# RasPi-BplusHAT_CamSlot.net
KiCad netlist of a schematic drawn in EAGLE
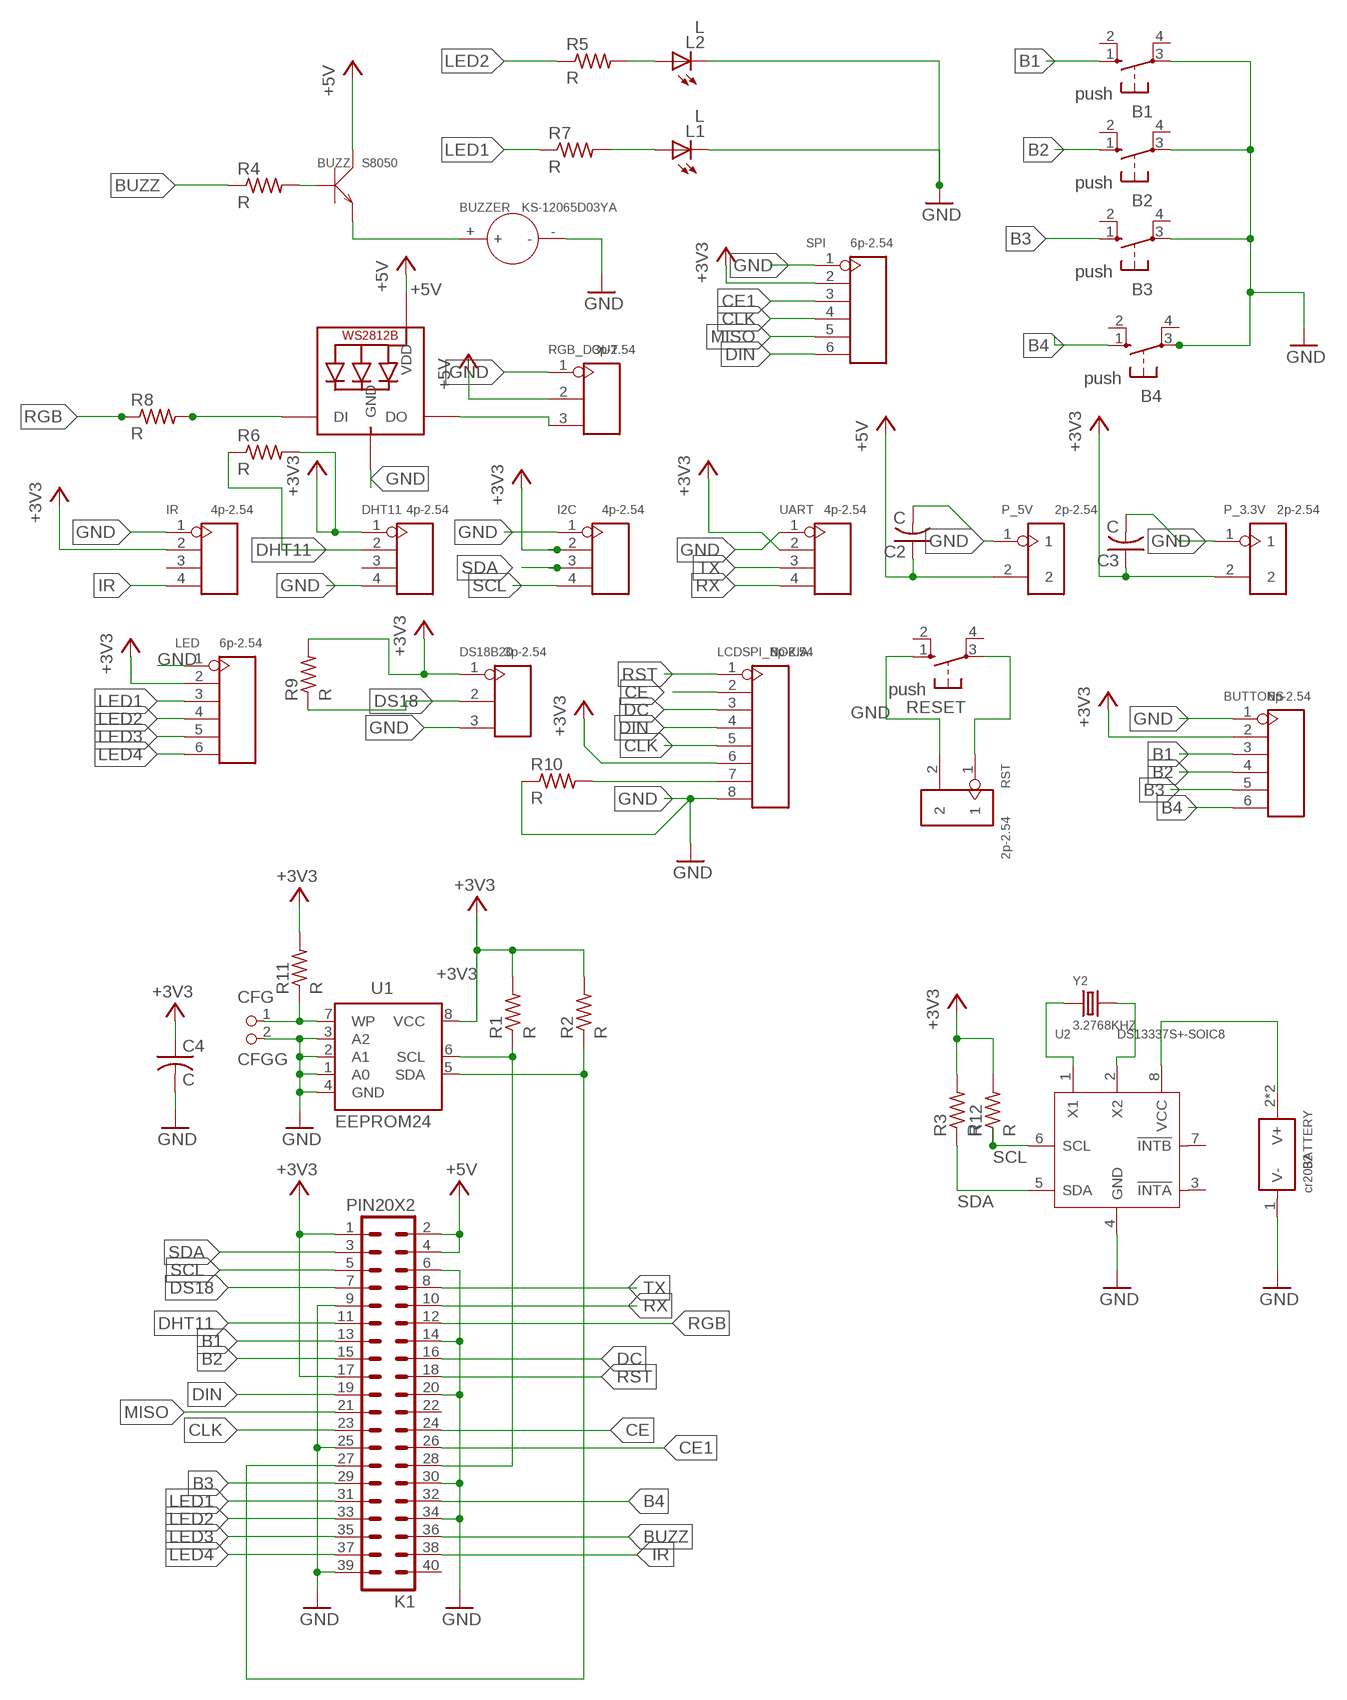
[diagram p0: schematic, sheet 1]

(export (version "E")
  (design (tool "Eeschema 10.0.6"))
  (components
    (comp (ref "B1")
      (value "push")
      (footprint "eagle-import:B3F-10XX")
      (fields (field (name "MPN") "B3F-1000"))
      (libsource (lib "eagle-import") (part "10-XX"))
    )
    (comp (ref "B2")
      (value "push")
      (footprint "eagle-import:B3F-10XX")
      (fields (field (name "MPN") "B3F-1000"))
      (libsource (lib "eagle-import") (part "10-XX"))
    )
    (comp (ref "B3")
      (value "push")
      (footprint "eagle-import:B3F-10XX")
      (fields (field (name "MPN") "B3F-1000"))
      (libsource (lib "eagle-import") (part "10-XX"))
    )
    (comp (ref "B4")
      (value "push")
      (footprint "eagle-import:B3F-10XX")
      (fields (field (name "MPN") "B3F-1000"))
      (libsource (lib "eagle-import") (part "10-XX"))
    )
    (comp (ref "BATTERY")
      (value "cr2032")
      (footprint "eagle-import:BAT2P-20.32-CR2032")
      (libsource (lib "eagle-import") (part "DIP-BATTERY-CELL-HOLDER(2032)"))
    )
    (comp (ref "BUTTONS")
      (value "6p-2.54")
      (footprint "eagle-import:H6-2.54")
      (fields (field (name "MPN") "F185-1106A1BSYC1"))
      (libsource (lib "eagle-import") (part "DIP-BLACK-FEMALE-HEADER-VERT(6P-2.54)"))
    )
    (comp (ref "BUZZ")
      (value "S8050")
      (footprint "eagle-import:SOT-23")
      (libsource (lib "eagle-import") (part "SMD-TRANSISTORS-NPN-25V-500MW-S8050(SOT-23)"))
    )
    (comp (ref "BUZZER")
      (value "KS-12065D03YA")
      (footprint "eagle-import:BZ2-7.6-D12.0XH6.5MM")
      (libsource (lib "eagle-import") (part "DIP-BUZZER-3V(KS-12065D03YA)"))
    )
    (comp (ref "C2")
      (value "C")
      (footprint "eagle-import:C1206")
      (libsource (lib "eagle-import") (part "C-USC1206"))
    )
    (comp (ref "C3")
      (value "C")
      (footprint "eagle-import:C1206")
      (libsource (lib "eagle-import") (part "C-USC1206"))
    )
    (comp (ref "C4")
      (value "C")
      (footprint "eagle-import:C1206")
      (libsource (lib "eagle-import") (part "C-USC1206"))
    )
    (comp (ref "CFG")
      (value "CFGG")
      (footprint "eagle-import:PIN_W_2")
      (libsource (lib "eagle-import") (part "PIN2_100"))
    )
    (comp (ref "DHT11")
      (value "4p-2.54")
      (footprint "eagle-import:H4-2.54")
      (fields (field (name "MPN") "F185-1104A1BSYA1"))
      (libsource (lib "eagle-import") (part "DIP-BLACK-FEMALE-HEADER-VERT(4P-2.54)"))
    )
    (comp (ref "DS18B20")
      (value "3p-2.54")
      (footprint "eagle-import:H3-2.54")
      (libsource (lib "eagle-import") (part "DIP-BLACK-MALE-HEADER-VERT(3P-2.54)"))
    )
    (comp (ref "I2C")
      (value "4p-2.54")
      (footprint "eagle-import:H4-2.54")
      (fields (field (name "MPN") "F185-1104A1BSYA1"))
      (libsource (lib "eagle-import") (part "DIP-BLACK-FEMALE-HEADER-VERT(4P-2.54)"))
    )
    (comp (ref "IR")
      (value "4p-2.54")
      (footprint "eagle-import:H4-2.54")
      (fields (field (name "MPN") "F185-1104A1BSYA1"))
      (libsource (lib "eagle-import") (part "DIP-BLACK-FEMALE-HEADER-VERT(4P-2.54)"))
    )
    (comp (ref "K1")
      (value "PIN20X2")
      (footprint "eagle-import:PIN_20X2")
      (libsource (lib "eagle-import") (part "PIN20X2"))
    )
    (comp (ref "L1")
      (value "L")
      (footprint "eagle-import:LED5MM")
      (libsource (lib "eagle-import") (part "LED5MM"))
    )
    (comp (ref "L2")
      (value "L")
      (footprint "eagle-import:LED5MM")
      (libsource (lib "eagle-import") (part "LED5MM"))
    )
    (comp (ref "LCDSPI_NOKIA")
      (value "8p-2.54")
      (footprint "eagle-import:H8-2.54")
      (fields (field (name "MPN") "F185-1108A1BSYC1"))
      (libsource (lib "eagle-import") (part "DIP-BLACK-FEMALE-HEADER-VERT(8P-2.54)"))
    )
    (comp (ref "LED")
      (value "6p-2.54")
      (footprint "eagle-import:H6-2.54")
      (fields (field (name "MPN") "P125-1106A1BS116A1"))
      (libsource (lib "eagle-import") (part "DIP-BLACK-MALE-HEADER(6P-2.54)"))
    )
    (comp (ref "P_3.3V")
      (value "2p-2.54")
      (footprint "eagle-import:H2-2.54")
      (fields (field (name "MPN") "P125-1102A0BS116A1"))
      (libsource (lib "eagle-import") (part "DIP-BLACK-MALE-HEADER-VERT(2P-2.54)"))
    )
    (comp (ref "P_5V")
      (value "2p-2.54")
      (footprint "eagle-import:H2-2.54")
      (fields (field (name "MPN") "P125-1102A0BS116A1"))
      (libsource (lib "eagle-import") (part "DIP-BLACK-MALE-HEADER-VERT(2P-2.54)"))
    )
    (comp (ref "R1")
      (value "R")
      (footprint "eagle-import:M1206")
      (libsource (lib "eagle-import") (part "R-US_M1206"))
    )
    (comp (ref "R2")
      (value "R")
      (footprint "eagle-import:M1206")
      (libsource (lib "eagle-import") (part "R-US_M1206"))
    )
    (comp (ref "R3")
      (value "R")
      (footprint "eagle-import:M1206")
      (libsource (lib "eagle-import") (part "R-US_M1206"))
    )
    (comp (ref "R4")
      (value "R")
      (footprint "eagle-import:M1206")
      (libsource (lib "eagle-import") (part "R-US_M1206"))
    )
    (comp (ref "R5")
      (value "R")
      (footprint "eagle-import:M1206")
      (libsource (lib "eagle-import") (part "R-US_M1206"))
    )
    (comp (ref "R6")
      (value "R")
      (footprint "eagle-import:M1206")
      (libsource (lib "eagle-import") (part "R-US_M1206"))
    )
    (comp (ref "R7")
      (value "R")
      (footprint "eagle-import:M1206")
      (libsource (lib "eagle-import") (part "R-US_M1206"))
    )
    (comp (ref "R8")
      (value "R")
      (footprint "eagle-import:M1206")
      (libsource (lib "eagle-import") (part "R-US_M1206"))
    )
    (comp (ref "R9")
      (value "R")
      (footprint "eagle-import:M1206")
      (libsource (lib "eagle-import") (part "R-US_M1206"))
    )
    (comp (ref "R10")
      (value "R")
      (footprint "eagle-import:M1206")
      (libsource (lib "eagle-import") (part "R-US_M1206"))
    )
    (comp (ref "R11")
      (value "R")
      (footprint "eagle-import:M1206")
      (libsource (lib "eagle-import") (part "R-US_M1206"))
    )
    (comp (ref "R12")
      (value "R")
      (footprint "eagle-import:M1206")
      (libsource (lib "eagle-import") (part "R-US_M1206"))
    )
    (comp (ref "RESET")
      (value "push")
      (footprint "eagle-import:B3F-10XX")
      (fields (field (name "MPN") "B3F-1000"))
      (libsource (lib "eagle-import") (part "10-XX"))
    )
    (comp (ref "RGB1")
      (value "WS2812B_5050N")
      (footprint "eagle-import:WS2812B-NARROW")
      (libsource (lib "eagle-import") (part "WS2812B_5050N"))
    )
    (comp (ref "RGB_DOUT")
      (value "3p-2.54")
      (footprint "eagle-import:H3-2.54")
      (libsource (lib "eagle-import") (part "DIP-BLACK-MALE-HEADER-VERT(3P-2.54)"))
    )
    (comp (ref "RST")
      (value "2p-2.54")
      (footprint "eagle-import:H2-2.54")
      (fields (field (name "MPN") "P125-1102A0BS116A1"))
      (libsource (lib "eagle-import") (part "DIP-BLACK-MALE-HEADER-VERT(2P-2.54)"))
    )
    (comp (ref "SPI")
      (value "6p-2.54")
      (footprint "eagle-import:H6-2.54")
      (fields (field (name "MPN") "F185-1106A1BSYC1"))
      (libsource (lib "eagle-import") (part "DIP-BLACK-FEMALE-HEADER-VERT(6P-2.54)"))
    )
    (comp (ref "U1")
      (value "EEPROM24")
      (footprint "eagle-import:SOIC8")
      (libsource (lib "eagle-import") (part "EEPROM24"))
    )
    (comp (ref "U2")
      (value "DS13337S+-SOIC8")
      (footprint "eagle-import:SOIC8-1.27-5X4MM")
      (fields (field (name "MPN") "DS1337S+"))
      (libsource (lib "eagle-import") (part "CLOCK-DS1337S+(SOIC8)"))
    )
    (comp (ref "UART")
      (value "4p-2.54")
      (footprint "eagle-import:H4-2.54")
      (fields (field (name "MPN") "P125-1104A0BS116A1"))
      (libsource (lib "eagle-import") (part "DIP-BLACK-MALE-HEADER-VERT(4P-2.54)"))
    )
    (comp (ref "Y2")
      (value "3.2768KHZ")
      (footprint "eagle-import:X2-SMD-L2.0X1.2X0.55MM")
      (fields (field (name "MPN") "FC-12M"))
      (libsource (lib "eagle-import") (part "SMD-CRYSTAL-32.768KHZ-12.5PF-20PPM-90K(2P-L2.0X1.2MM)"))
    )
  )
  (nets
    (net (code "1") (name "+3V3") (class "Default")
      (node (ref "BUTTONS") (pin "2") (pinfunction "2_2") (pintype "bidirectional"))
      (node (ref "C3") (pin "1") (pinfunction "1_1") (pintype "passive"))
      (node (ref "C4") (pin "1") (pinfunction "1_1") (pintype "passive"))
      (node (ref "DHT11") (pin "1") (pinfunction "P$1_1") (pintype "bidirectional"))
      (node (ref "DS18B20") (pin "1") (pinfunction "P$1_1") (pintype "bidirectional"))
      (node (ref "I2C") (pin "2") (pinfunction "P$2_2") (pintype "bidirectional"))
      (node (ref "IR") (pin "2") (pinfunction "P$2_2") (pintype "bidirectional"))
      (node (ref "K1") (pin "1") (pinfunction "1_1") (pintype "passive"))
      (node (ref "K1") (pin "17") (pinfunction "17_17") (pintype "passive"))
      (node (ref "LCDSPI_NOKIA") (pin "6") (pinfunction "6_6") (pintype "bidirectional"))
      (node (ref "LED") (pin "2") (pinfunction "2_2") (pintype "bidirectional"))
      (node (ref "P_3.3V") (pin "2") (pinfunction "2_2") (pintype "bidirectional"))
      (node (ref "R1") (pin "2") (pinfunction "2_2") (pintype "passive"))
      (node (ref "R11") (pin "2") (pinfunction "2_2") (pintype "passive"))
      (node (ref "R12") (pin "2") (pinfunction "2_2") (pintype "passive"))
      (node (ref "R2") (pin "2") (pinfunction "2_2") (pintype "passive"))
      (node (ref "R3") (pin "2") (pinfunction "2_2") (pintype "passive"))
      (node (ref "R6") (pin "2") (pinfunction "2_2") (pintype "passive"))
      (node (ref "R9") (pin "2") (pinfunction "2_2") (pintype "passive"))
      (node (ref "SPI") (pin "2") (pinfunction "2_2") (pintype "bidirectional"))
      (node (ref "U1") (pin "8") (pinfunction "VCC_8") (pintype "power_in"))
      (node (ref "UART") (pin "2") (pinfunction "P$2_2") (pintype "bidirectional"))
    )
    (net (code "2") (name "+5V") (class "Default")
      (node (ref "BUZZ") (pin "3") (pinfunction "C_3") (pintype "passive"))
      (node (ref "C2") (pin "1") (pinfunction "1_1") (pintype "passive"))
      (node (ref "K1") (pin "2") (pinfunction "2_2") (pintype "passive"))
      (node (ref "K1") (pin "4") (pinfunction "4_4") (pintype "passive"))
      (node (ref "P_5V") (pin "2") (pinfunction "2_2") (pintype "bidirectional"))
      (node (ref "RGB1") (pin "1-VDD") (pinfunction "VDD_1-VDD") (pintype "power_in"))
      (node (ref "RGB_DOUT") (pin "2") (pinfunction "P$2_2") (pintype "bidirectional"))
    )
    (net (code "3") (name "B1") (class "Default")
      (node (ref "B1") (pin "1") (pinfunction "S_1") (pintype "passive"))
      (node (ref "BUTTONS") (pin "3") (pinfunction "3_3") (pintype "bidirectional"))
      (node (ref "K1") (pin "13") (pinfunction "13_13") (pintype "passive"))
    )
    (net (code "4") (name "B2") (class "Default")
      (node (ref "B2") (pin "1") (pinfunction "S_1") (pintype "passive"))
      (node (ref "BUTTONS") (pin "4") (pinfunction "4_4") (pintype "bidirectional"))
      (node (ref "K1") (pin "15") (pinfunction "15_15") (pintype "passive"))
    )
    (net (code "5") (name "B3") (class "Default")
      (node (ref "B3") (pin "1") (pinfunction "S_1") (pintype "passive"))
      (node (ref "BUTTONS") (pin "5") (pinfunction "5_5") (pintype "bidirectional"))
      (node (ref "K1") (pin "29") (pinfunction "29_29") (pintype "passive"))
    )
    (net (code "6") (name "B4") (class "Default")
      (node (ref "B4") (pin "1") (pinfunction "S_1") (pintype "passive"))
      (node (ref "BUTTONS") (pin "6") (pinfunction "6_6") (pintype "bidirectional"))
      (node (ref "K1") (pin "32") (pinfunction "32_32") (pintype "passive"))
    )
    (net (code "7") (name "BUZZ") (class "Default")
      (node (ref "K1") (pin "36") (pinfunction "36_36") (pintype "passive"))
      (node (ref "R4") (pin "1") (pinfunction "1_1") (pintype "passive"))
    )
    (net (code "8") (name "CE") (class "Default")
      (node (ref "K1") (pin "24") (pinfunction "24_24") (pintype "passive"))
      (node (ref "LCDSPI_NOKIA") (pin "2") (pinfunction "2_2") (pintype "bidirectional"))
    )
    (net (code "9") (name "CE1") (class "Default")
      (node (ref "K1") (pin "26") (pinfunction "26_26") (pintype "passive"))
      (node (ref "SPI") (pin "3") (pinfunction "3_3") (pintype "bidirectional"))
    )
    (net (code "10") (name "CLK") (class "Default")
      (node (ref "K1") (pin "23") (pinfunction "23_23") (pintype "passive"))
      (node (ref "LCDSPI_NOKIA") (pin "5") (pinfunction "5_5") (pintype "bidirectional"))
      (node (ref "SPI") (pin "4") (pinfunction "4_4") (pintype "bidirectional"))
    )
    (net (code "11") (name "DC") (class "Default")
      (node (ref "K1") (pin "16") (pinfunction "16_16") (pintype "passive"))
      (node (ref "LCDSPI_NOKIA") (pin "3") (pinfunction "3_3") (pintype "bidirectional"))
    )
    (net (code "12") (name "DHT11") (class "Default")
      (node (ref "DHT11") (pin "2") (pinfunction "P$2_2") (pintype "bidirectional"))
      (node (ref "K1") (pin "11") (pinfunction "11_11") (pintype "passive"))
      (node (ref "R6") (pin "1") (pinfunction "1_1") (pintype "passive"))
    )
    (net (code "13") (name "DIN") (class "Default")
      (node (ref "K1") (pin "19") (pinfunction "19_19") (pintype "passive"))
      (node (ref "LCDSPI_NOKIA") (pin "4") (pinfunction "4_4") (pintype "bidirectional"))
      (node (ref "SPI") (pin "6") (pinfunction "6_6") (pintype "bidirectional"))
    )
    (net (code "14") (name "DS18") (class "Default")
      (node (ref "DS18B20") (pin "2") (pinfunction "P$2_2") (pintype "bidirectional"))
      (node (ref "K1") (pin "7") (pinfunction "7_7") (pintype "passive"))
      (node (ref "R9") (pin "1") (pinfunction "1_1") (pintype "passive"))
    )
    (net (code "15") (name "GND") (class "Default")
      (node (ref "B1") (pin "3") (pinfunction "P_3") (pintype "passive"))
      (node (ref "B2") (pin "3") (pinfunction "P_3") (pintype "passive"))
      (node (ref "B3") (pin "3") (pinfunction "P_3") (pintype "passive"))
      (node (ref "B4") (pin "3") (pinfunction "P_3") (pintype "passive"))
      (node (ref "BATTERY") (pin "1") (pinfunction "V-_1") (pintype "bidirectional"))
      (node (ref "BUTTONS") (pin "1") (pinfunction "1_1") (pintype "bidirectional"))
      (node (ref "BUZZER") (pin "-") (pinfunction "-_-") (pintype "bidirectional"))
      (node (ref "C2") (pin "2") (pinfunction "2_2") (pintype "passive"))
      (node (ref "C3") (pin "2") (pinfunction "2_2") (pintype "passive"))
      (node (ref "C4") (pin "2") (pinfunction "2_2") (pintype "passive"))
      (node (ref "CFG") (pin "2") (pinfunction "2_2") (pintype "passive"))
      (node (ref "DHT11") (pin "4") (pinfunction "P$4_4") (pintype "bidirectional"))
      (node (ref "DS18B20") (pin "3") (pinfunction "P$3_3") (pintype "bidirectional"))
      (node (ref "I2C") (pin "1") (pinfunction "P$1_1") (pintype "bidirectional"))
      (node (ref "IR") (pin "1") (pinfunction "P$1_1") (pintype "bidirectional"))
      (node (ref "K1") (pin "14") (pinfunction "14_14") (pintype "passive"))
      (node (ref "K1") (pin "20") (pinfunction "20_20") (pintype "passive"))
      (node (ref "K1") (pin "25") (pinfunction "25_25") (pintype "passive"))
      (node (ref "K1") (pin "30") (pinfunction "30_30") (pintype "passive"))
      (node (ref "K1") (pin "34") (pinfunction "34_34") (pintype "passive"))
      (node (ref "K1") (pin "39") (pinfunction "39_39") (pintype "passive"))
      (node (ref "K1") (pin "6") (pinfunction "6_6") (pintype "passive"))
      (node (ref "K1") (pin "9") (pinfunction "9_9") (pintype "passive"))
      (node (ref "L1") (pin "K") (pinfunction "C_K") (pintype "passive"))
      (node (ref "L2") (pin "K") (pinfunction "C_K") (pintype "passive"))
      (node (ref "LCDSPI_NOKIA") (pin "8") (pinfunction "8_8") (pintype "bidirectional"))
      (node (ref "LED") (pin "1") (pinfunction "1_1") (pintype "bidirectional"))
      (node (ref "P_3.3V") (pin "1") (pinfunction "1_1") (pintype "bidirectional"))
      (node (ref "P_5V") (pin "1") (pinfunction "1_1") (pintype "bidirectional"))
      (node (ref "R10") (pin "1") (pinfunction "1_1") (pintype "passive"))
      (node (ref "RESET") (pin "1") (pinfunction "S_1") (pintype "passive"))
      (node (ref "RGB1") (pin "3-GND") (pinfunction "GND_3-GND") (pintype "power_in"))
      (node (ref "RGB_DOUT") (pin "1") (pinfunction "P$1_1") (pintype "bidirectional"))
      (node (ref "RST") (pin "2") (pinfunction "2_2") (pintype "bidirectional"))
      (node (ref "SPI") (pin "1") (pinfunction "1_1") (pintype "bidirectional"))
      (node (ref "U1") (pin "1") (pinfunction "A0_1") (pintype "input"))
      (node (ref "U1") (pin "2") (pinfunction "A1_2") (pintype "input"))
      (node (ref "U1") (pin "3") (pinfunction "A2_3") (pintype "input"))
      (node (ref "U1") (pin "4") (pinfunction "GND_4") (pintype "power_in"))
      (node (ref "U2") (pin "4") (pinfunction "GND_4") (pintype "bidirectional"))
      (node (ref "UART") (pin "1") (pinfunction "P$1_1") (pintype "bidirectional"))
    )
    (net (code "16") (name "IR") (class "Default")
      (node (ref "IR") (pin "4") (pinfunction "P$4_4") (pintype "bidirectional"))
      (node (ref "K1") (pin "38") (pinfunction "38_38") (pintype "passive"))
    )
    (net (code "17") (name "LED1") (class "Default")
      (node (ref "K1") (pin "31") (pinfunction "31_31") (pintype "passive"))
      (node (ref "LED") (pin "3") (pinfunction "3_3") (pintype "bidirectional"))
      (node (ref "R7") (pin "1") (pinfunction "1_1") (pintype "passive"))
    )
    (net (code "18") (name "LED2") (class "Default")
      (node (ref "K1") (pin "33") (pinfunction "33_33") (pintype "passive"))
      (node (ref "LED") (pin "4") (pinfunction "4_4") (pintype "bidirectional"))
      (node (ref "R5") (pin "1") (pinfunction "1_1") (pintype "passive"))
    )
    (net (code "19") (name "LED3") (class "Default")
      (node (ref "K1") (pin "35") (pinfunction "35_35") (pintype "passive"))
      (node (ref "LED") (pin "5") (pinfunction "5_5") (pintype "bidirectional"))
    )
    (net (code "20") (name "LED4") (class "Default")
      (node (ref "K1") (pin "37") (pinfunction "37_37") (pintype "passive"))
      (node (ref "LED") (pin "6") (pinfunction "6_6") (pintype "bidirectional"))
    )
    (net (code "21") (name "MISO") (class "Default")
      (node (ref "K1") (pin "21") (pinfunction "21_21") (pintype "passive"))
      (node (ref "SPI") (pin "5") (pinfunction "5_5") (pintype "bidirectional"))
    )
    (net (code "22") (name "Net-(BUZZ-B)") (class "Default")
      (node (ref "BUZZ") (pin "1") (pinfunction "B_1") (pintype "passive"))
      (node (ref "R4") (pin "2") (pinfunction "2_2") (pintype "passive"))
    )
    (net (code "23") (name "Net-(BUZZ-E)") (class "Default")
      (node (ref "BUZZ") (pin "2") (pinfunction "E_2") (pintype "passive"))
      (node (ref "BUZZER") (pin "+") (pinfunction "+_+") (pintype "bidirectional"))
    )
    (net (code "24") (name "Net-(L1-PadA)") (class "Default")
      (node (ref "L1") (pin "A") (pinfunction "A_A") (pintype "passive"))
      (node (ref "R7") (pin "2") (pinfunction "2_2") (pintype "passive"))
    )
    (net (code "25") (name "Net-(L2-PadA)") (class "Default")
      (node (ref "L2") (pin "A") (pinfunction "A_A") (pintype "passive"))
      (node (ref "R5") (pin "2") (pinfunction "2_2") (pintype "passive"))
    )
    (net (code "26") (name "Net-(LCDSPI_NOKIA-Pad7)") (class "Default")
      (node (ref "LCDSPI_NOKIA") (pin "7") (pinfunction "7_7") (pintype "bidirectional"))
      (node (ref "R10") (pin "2") (pinfunction "2_2") (pintype "passive"))
    )
    (net (code "27") (name "Net-(RESET-P)") (class "Default")
      (node (ref "RESET") (pin "3") (pinfunction "P_3") (pintype "passive"))
      (node (ref "RST") (pin "1") (pinfunction "1_1") (pintype "bidirectional"))
    )
    (net (code "28") (name "Net-(RGB1-DI)") (class "Default")
      (node (ref "R8") (pin "2") (pinfunction "2_2") (pintype "passive"))
      (node (ref "RGB1") (pin "4-DIN") (pinfunction "DI_4-DIN") (pintype "input"))
    )
    (net (code "29") (name "Net-(RGB1-DO)") (class "Default")
      (node (ref "RGB1") (pin "2-DOUT") (pinfunction "DO_2-DOUT") (pintype "output"))
      (node (ref "RGB_DOUT") (pin "3") (pinfunction "P$3_3") (pintype "bidirectional"))
    )
    (net (code "30") (name "Net-(U1-SCL)") (class "Default")
      (node (ref "K1") (pin "28") (pinfunction "28_28") (pintype "passive"))
      (node (ref "R1") (pin "1") (pinfunction "1_1") (pintype "passive"))
      (node (ref "U1") (pin "6") (pinfunction "SCL_6") (pintype "input"))
    )
    (net (code "31") (name "Net-(U1-SDA)") (class "Default")
      (node (ref "K1") (pin "27") (pinfunction "27_27") (pintype "passive"))
      (node (ref "R2") (pin "1") (pinfunction "1_1") (pintype "passive"))
      (node (ref "U1") (pin "5") (pinfunction "SDA_5") (pintype "bidirectional"))
    )
    (net (code "32") (name "Net-(U1-WP)") (class "Default")
      (node (ref "CFG") (pin "1") (pinfunction "1_1") (pintype "passive"))
      (node (ref "R11") (pin "1") (pinfunction "1_1") (pintype "passive"))
      (node (ref "U1") (pin "7") (pinfunction "WP_7") (pintype "input"))
    )
    (net (code "33") (name "Net-(U2-VCC)") (class "Default")
      (node (ref "BATTERY") (pin "2") (pinfunction "V+_2") (pintype "bidirectional"))
      (node (ref "BATTERY") (pin "3") (pinfunction "V+_3") (pintype "bidirectional"))
      (node (ref "U2") (pin "8") (pinfunction "VCC_8") (pintype "bidirectional"))
    )
    (net (code "34") (name "Net-(U2-X1)") (class "Default")
      (node (ref "U2") (pin "1") (pinfunction "X1_1") (pintype "bidirectional"))
      (node (ref "Y2") (pin "1") (pinfunction "1_1") (pintype "passive"))
    )
    (net (code "35") (name "Net-(U2-X2)") (class "Default")
      (node (ref "U2") (pin "2") (pinfunction "X2_2") (pintype "bidirectional"))
      (node (ref "Y2") (pin "2") (pinfunction "2_2") (pintype "passive"))
    )
    (net (code "36") (name "RGB") (class "Default")
      (node (ref "K1") (pin "12") (pinfunction "12_12") (pintype "passive"))
      (node (ref "R8") (pin "1") (pinfunction "1_1") (pintype "passive"))
    )
    (net (code "37") (name "RST") (class "Default")
      (node (ref "K1") (pin "18") (pinfunction "18_18") (pintype "passive"))
      (node (ref "LCDSPI_NOKIA") (pin "1") (pinfunction "1_1") (pintype "bidirectional"))
    )
    (net (code "38") (name "RX") (class "Default")
      (node (ref "K1") (pin "10") (pinfunction "10_10") (pintype "passive"))
      (node (ref "UART") (pin "4") (pinfunction "P$4_4") (pintype "bidirectional"))
    )
    (net (code "39") (name "SCL") (class "Default")
      (node (ref "I2C") (pin "4") (pinfunction "P$4_4") (pintype "bidirectional"))
      (node (ref "K1") (pin "5") (pinfunction "5_5") (pintype "passive"))
      (node (ref "R12") (pin "1") (pinfunction "1_1") (pintype "passive"))
      (node (ref "U2") (pin "6") (pinfunction "SCL_6") (pintype "bidirectional"))
    )
    (net (code "40") (name "SDA") (class "Default")
      (node (ref "I2C") (pin "3") (pinfunction "P$3_3") (pintype "bidirectional"))
      (node (ref "K1") (pin "3") (pinfunction "3_3") (pintype "passive"))
      (node (ref "R3") (pin "1") (pinfunction "1_1") (pintype "passive"))
      (node (ref "U2") (pin "5") (pinfunction "SDA_5") (pintype "bidirectional"))
    )
    (net (code "41") (name "TX") (class "Default")
      (node (ref "K1") (pin "8") (pinfunction "8_8") (pintype "passive"))
      (node (ref "UART") (pin "3") (pinfunction "P$3_3") (pintype "bidirectional"))
    )
    (net (code "42") (name "unconnected-(B1-P1-Pad4)") (class "Default")
      (node (ref "B1") (pin "4") (pinfunction "P1_4") (pintype "passive"))
    )
    (net (code "43") (name "unconnected-(B1-S1-Pad2)") (class "Default")
      (node (ref "B1") (pin "2") (pinfunction "S1_2") (pintype "passive"))
    )
    (net (code "44") (name "unconnected-(B2-P1-Pad4)") (class "Default")
      (node (ref "B2") (pin "4") (pinfunction "P1_4") (pintype "passive"))
    )
    (net (code "45") (name "unconnected-(B2-S1-Pad2)") (class "Default")
      (node (ref "B2") (pin "2") (pinfunction "S1_2") (pintype "passive"))
    )
    (net (code "46") (name "unconnected-(B3-P1-Pad4)") (class "Default")
      (node (ref "B3") (pin "4") (pinfunction "P1_4") (pintype "passive"))
    )
    (net (code "47") (name "unconnected-(B3-S1-Pad2)") (class "Default")
      (node (ref "B3") (pin "2") (pinfunction "S1_2") (pintype "passive"))
    )
    (net (code "48") (name "unconnected-(B4-P1-Pad4)") (class "Default")
      (node (ref "B4") (pin "4") (pinfunction "P1_4") (pintype "passive"))
    )
    (net (code "49") (name "unconnected-(B4-S1-Pad2)") (class "Default")
      (node (ref "B4") (pin "2") (pinfunction "S1_2") (pintype "passive"))
    )
    (net (code "50") (name "unconnected-(DHT11-P$3-Pad3)") (class "Default")
      (node (ref "DHT11") (pin "3") (pinfunction "P$3_3") (pintype "bidirectional"))
    )
    (net (code "51") (name "unconnected-(IR-P$3-Pad3)") (class "Default")
      (node (ref "IR") (pin "3") (pinfunction "P$3_3") (pintype "bidirectional"))
    )
    (net (code "52") (name "unconnected-(K1-Pad22)") (class "Default")
      (node (ref "K1") (pin "22") (pinfunction "22_22") (pintype "passive"))
    )
    (net (code "53") (name "unconnected-(K1-Pad40)") (class "Default")
      (node (ref "K1") (pin "40") (pinfunction "40_40") (pintype "passive"))
    )
    (net (code "54") (name "unconnected-(RESET-P1-Pad4)") (class "Default")
      (node (ref "RESET") (pin "4") (pinfunction "P1_4") (pintype "passive"))
    )
    (net (code "55") (name "unconnected-(RESET-S1-Pad2)") (class "Default")
      (node (ref "RESET") (pin "2") (pinfunction "S1_2") (pintype "passive"))
    )
    (net (code "56") (name "unconnected-(U2-~{INTA}-Pad3)") (class "Default")
      (node (ref "U2") (pin "3") (pinfunction "~{INTA}_3") (pintype "bidirectional"))
    )
    (net (code "57") (name "unconnected-(U2-~{INTB}-Pad7)") (class "Default")
      (node (ref "U2") (pin "7") (pinfunction "~{INTB}_7") (pintype "bidirectional"))
    )
  )
)
